# STM32_Schematic.net
KiCad netlist of a schematic drawn in Altium Designer
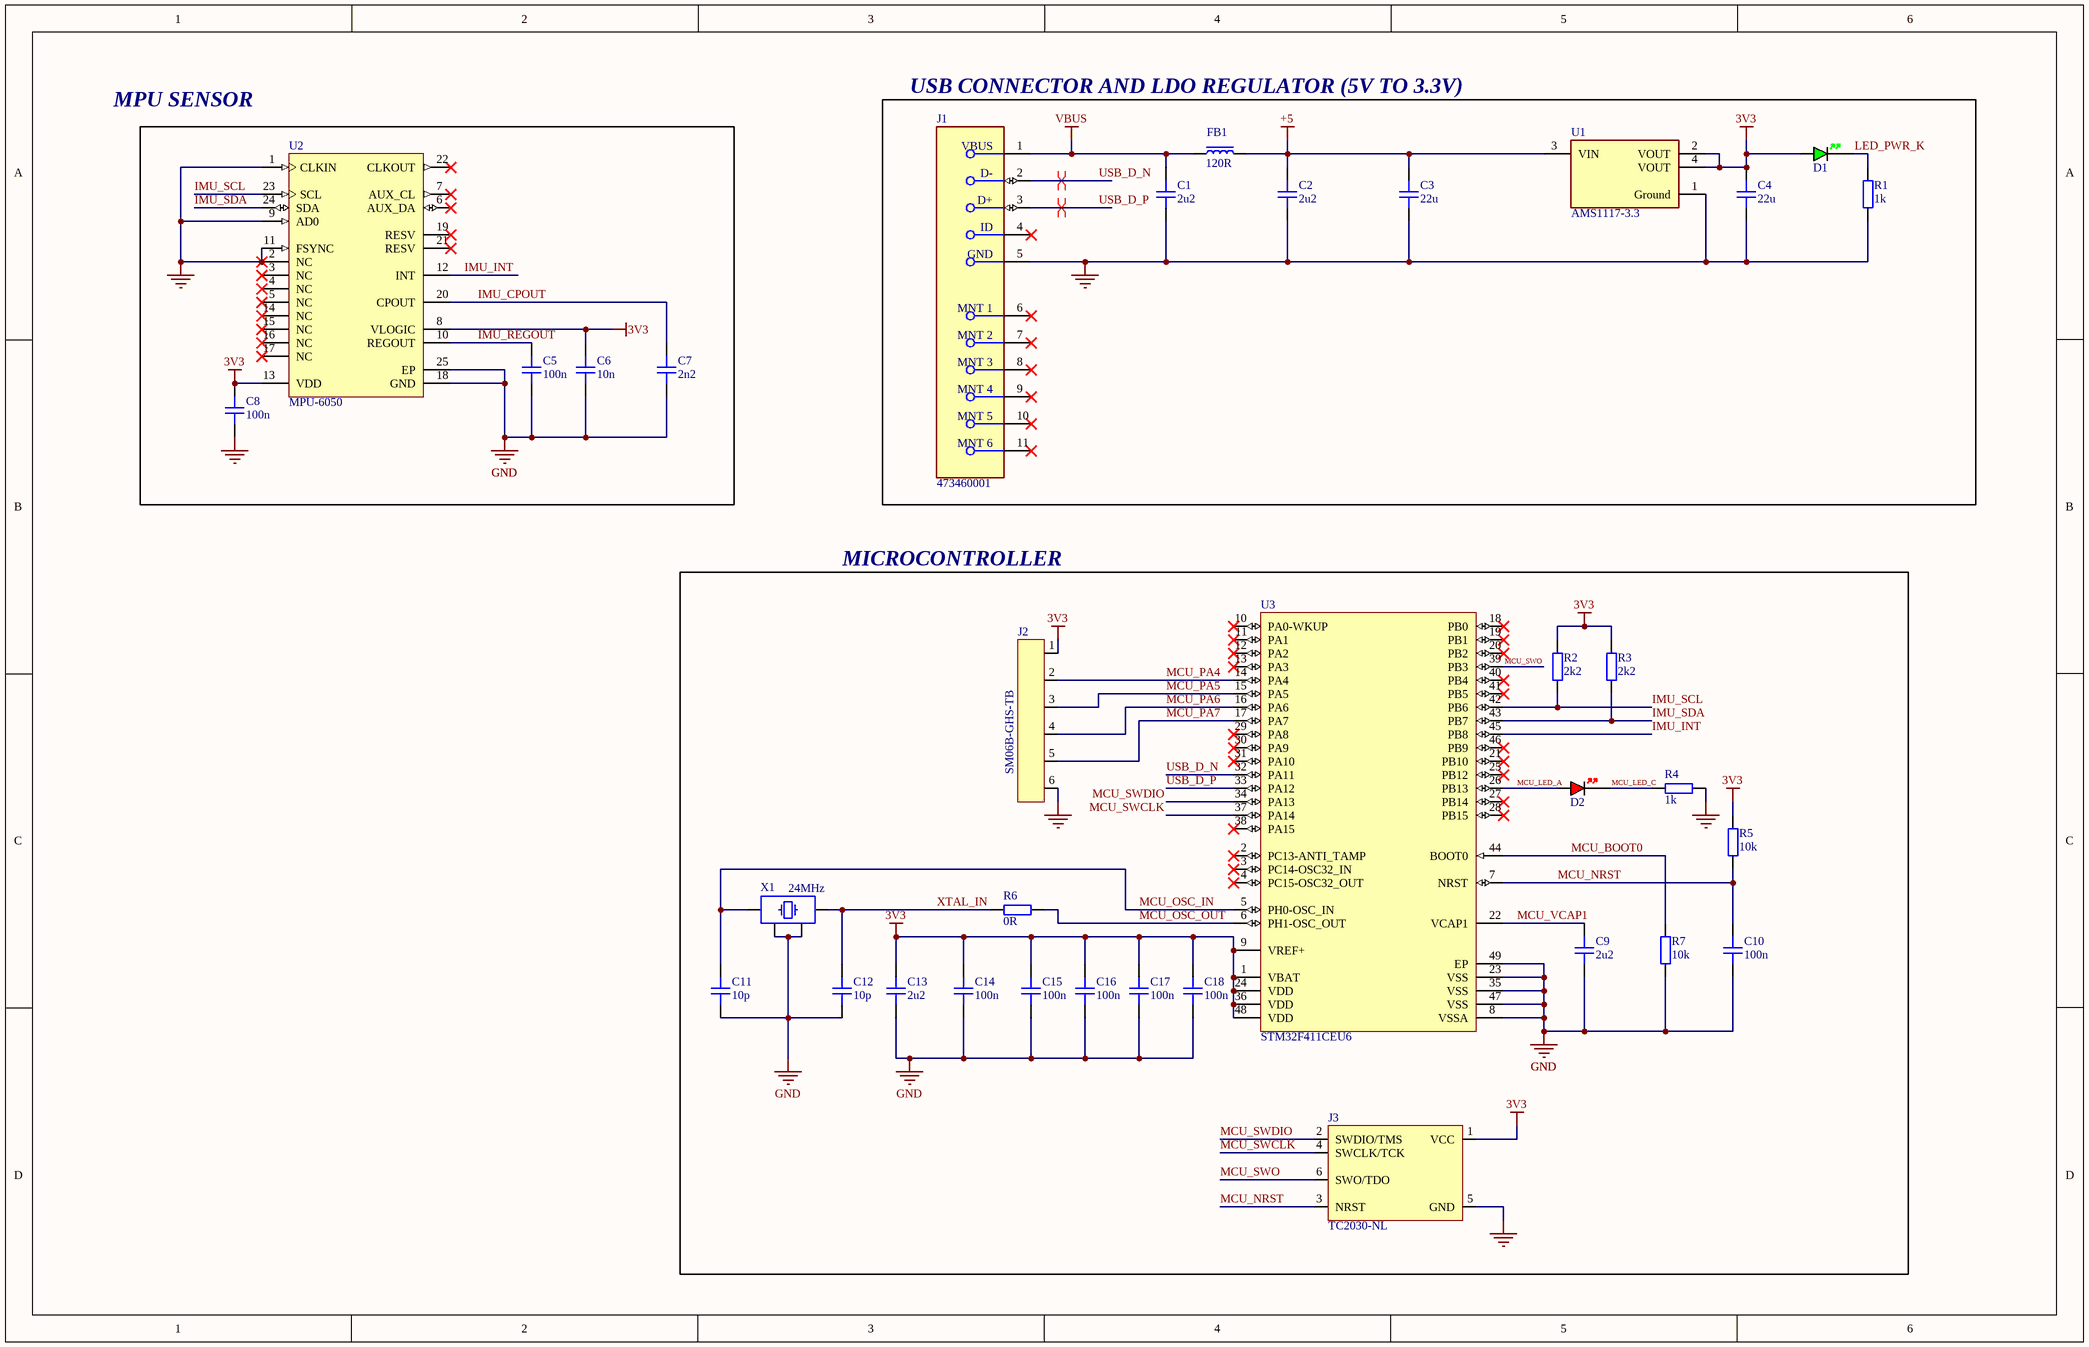
[diagram p0: STM32_Schematic.SchDoc]

(export (version "E")
  (design (tool "Eeschema 10.0.6"))
  (components
    (comp (ref "C1")
      (value "2u2")
      (footprint "CAP_0603")
      (description "Capacitor SMD 0603")
      (libsource (lib "Schematic-Lib-PhilsLab") (part "CAP_0603"))
    )
    (comp (ref "C2")
      (value "2u2")
      (footprint "CAP_0603")
      (description "Capacitor SMD 0603")
      (libsource (lib "Schematic-Lib-PhilsLab") (part "CAP_0603"))
    )
    (comp (ref "C3")
      (value "22u")
      (footprint "CAP_0805")
      (description "Capacitor SMD 0805")
      (libsource (lib "Schematic-Lib-PhilsLab") (part "CAP_0805"))
    )
    (comp (ref "C4")
      (value "22u")
      (footprint "CAP_0805")
      (description "Capacitor SMD 0805")
      (libsource (lib "Schematic-Lib-PhilsLab") (part "CAP_0805"))
    )
    (comp (ref "C5")
      (value "100n")
      (footprint "CAP_0402")
      (description "Capacitor SMD 0402")
      (libsource (lib "Schematic-Lib-PhilsLab") (part "CAP_0402"))
    )
    (comp (ref "C6")
      (value "10n")
      (footprint "CAP_0402")
      (description "Capacitor SMD 0402")
      (libsource (lib "Schematic-Lib-PhilsLab") (part "CAP_0402"))
    )
    (comp (ref "C7")
      (value "2n2")
      (footprint "CAP_0402")
      (description "Capacitor SMD 0402")
      (libsource (lib "Schematic-Lib-PhilsLab") (part "CAP_0402"))
    )
    (comp (ref "C8")
      (value "100n")
      (footprint "CAP_0402")
      (description "Capacitor SMD 0402")
      (libsource (lib "Schematic-Lib-PhilsLab") (part "CAP_0402"))
    )
    (comp (ref "C9")
      (value "2u2")
      (footprint "CAP_0603")
      (description "Capacitor SMD 0603")
      (libsource (lib "Schematic-Lib-PhilsLab") (part "CAP_0603"))
    )
    (comp (ref "C10")
      (value "100n")
      (footprint "CAP_0402")
      (description "Capacitor SMD 0402")
      (libsource (lib "Schematic-Lib-PhilsLab") (part "CAP_0402"))
    )
    (comp (ref "C11")
      (value "10p")
      (footprint "CAP_0402")
      (description "Capacitor SMD 0402")
      (libsource (lib "Schematic-Lib-PhilsLab") (part "CAP_0402"))
    )
    (comp (ref "C12")
      (value "10p")
      (footprint "CAP_0402")
      (description "Capacitor SMD 0402")
      (libsource (lib "Schematic-Lib-PhilsLab") (part "CAP_0402"))
    )
    (comp (ref "C13")
      (value "2u2")
      (footprint "CAP_0603")
      (description "Capacitor SMD 0603")
      (libsource (lib "Schematic-Lib-PhilsLab") (part "CAP_0603"))
    )
    (comp (ref "C14")
      (value "100n")
      (footprint "CAP_0402")
      (description "Capacitor SMD 0402")
      (libsource (lib "Schematic-Lib-PhilsLab") (part "CAP_0402"))
    )
    (comp (ref "C15")
      (value "100n")
      (footprint "CAP_0402")
      (description "Capacitor SMD 0402")
      (libsource (lib "Schematic-Lib-PhilsLab") (part "CAP_0402"))
    )
    (comp (ref "C16")
      (value "100n")
      (footprint "CAP_0402")
      (description "Capacitor SMD 0402")
      (libsource (lib "Schematic-Lib-PhilsLab") (part "CAP_0402"))
    )
    (comp (ref "C17")
      (value "100n")
      (footprint "CAP_0402")
      (description "Capacitor SMD 0402")
      (libsource (lib "Schematic-Lib-PhilsLab") (part "CAP_0402"))
    )
    (comp (ref "C18")
      (value "100n")
      (footprint "CAP_0402")
      (description "Capacitor SMD 0402")
      (libsource (lib "Schematic-Lib-PhilsLab") (part "CAP_0402"))
    )
    (comp (ref "D1")
      (value "GREEN")
      (footprint "LED_0402_GREEN")
      (description "LED 0402 GREEN SMD")
      (libsource (lib "Schematic-Lib-PhilsLab") (part "LED_0402_GREEN"))
    )
    (comp (ref "D2")
      (value "RED")
      (footprint "LED_0402_RED")
      (description "LED 0402 RED SMD")
      (libsource (lib "Schematic-Lib-PhilsLab") (part "LED_0402_RED"))
    )
    (comp (ref "FB1")
      (value "120R")
      (footprint "FB_0603")
      (description "Ferrite Bead SMD 0603")
      (libsource (lib "Schematic-Lib-PhilsLab") (part "FB_0603"))
    )
    (comp (ref "J1")
      (value "473460001")
      (footprint "FP-473460001-MFG")
      (description "CONN RCPT USB2.0 MICRO B SMD R/A")
      (fields
        (field (name "OCTOPART") "https://octopart.com/47346-0001-molex-7164928")
        (field (name "MANUFACTURER") "Molex")
      )
      (libsource (lib "Altium Content Vault") (part "53ae1f1d9b557310b43ca686e5bb76a"))
    )
    (comp (ref "J2")
      (value "SM06B-GHS-TB")
      (footprint "SM06B-GHS-TB")
      (description "Header Connector 6 Position 1.25MM Pitch SMD Horizontal JST GH")
      (fields (field (name "MANUFACTURER") "JST"))
      (libsource (lib "Schematic-Lib-PhilsLab") (part "SM06B-GHS-TB"))
    )
    (comp (ref "J3")
      (value "TC2030-NL")
      (footprint "TC2030-NL-FP")
      (description "Tag-Connect No-Solder SWD Debug Connector (No Legs) DO NOT PLACE")
      (fields
        (field (name "MANUFACTURER") "Tag-Connect")
        (field (name "MANUFACTURER PART NUMBER") "TC2030-NL-FP")
      )
      (libsource (lib "Schematic-Lib-PhilsLab") (part "TC2030-NL"))
    )
    (comp (ref "R1")
      (value "1k")
      (footprint "RES_0402")
      (description "Resistor SMD 0402")
      (libsource (lib "Schematic-Lib-PhilsLab") (part "RES_0402"))
    )
    (comp (ref "R2")
      (value "2k2")
      (footprint "RES_0402")
      (description "Resistor SMD 0402")
      (libsource (lib "Schematic-Lib-PhilsLab") (part "RES_0402"))
    )
    (comp (ref "R3")
      (value "2k2")
      (footprint "RES_0402")
      (description "Resistor SMD 0402")
      (libsource (lib "Schematic-Lib-PhilsLab") (part "RES_0402"))
    )
    (comp (ref "R4")
      (value "1k")
      (footprint "RES_0402")
      (description "Resistor SMD 0402")
      (libsource (lib "Schematic-Lib-PhilsLab") (part "RES_0402"))
    )
    (comp (ref "R5")
      (value "10k")
      (footprint "RES_0402")
      (description "Resistor SMD 0402")
      (libsource (lib "Schematic-Lib-PhilsLab") (part "RES_0402"))
    )
    (comp (ref "R6")
      (value "0R")
      (footprint "RES_0402")
      (description "Resistor SMD 0402")
      (libsource (lib "Schematic-Lib-PhilsLab") (part "RES_0402"))
    )
    (comp (ref "R7")
      (value "10k")
      (footprint "RES_0402")
      (description "Resistor SMD 0402")
      (libsource (lib "Schematic-Lib-PhilsLab") (part "RES_0402"))
    )
    (comp (ref "U1")
      (value "AMS1117-3.3")
      (footprint "FP-AMS1117-IPC_C")
      (description "LDO Voltage Regulators 1A, 3.3V")
      (fields
        (field (name "OCTOPART") "https://octopart.com/ams1117-3.3-advanced+monolithic+systems-25899300")
        (field (name "MANUFACTURER") "Advanced Monolithic Systems")
      )
      (libsource (lib "Altium Content Vault") (part "8bdbb5f8e77002000e30dd2845d0354"))
    )
    (comp (ref "U2")
      (value "MPU-6050")
      (footprint "IS-QFN-24_V")
      (fields (field (name "MANUFACTURER") "InvenSense"))
      (libsource (lib "Altium Content Vault") (part "IS-MPU-6050-QFN-24"))
    )
    (comp (ref "U3")
      (value "STM32F411CEU6")
      (footprint "STM-UFQFPN48_L")
      (libsource (lib "Altium Content Vault") (part "MC-ARM-STM32F411-UFQFPN48"))
    )
    (comp (ref "X1")
      (value "24MHz")
      (footprint "XTAL_3225")
      (description "Crystal SMD 24MHz 10PPM 7pF 3225")
      (fields
        (field (name "MANUFACTURER") "Epson")
        (field (name "MANUFACTURER PART NUMBER") "TSX-3225 24.0000MF15X-AC")
      )
      (libsource (lib "Schematic-Lib-PhilsLab") (part "TSX-3225_24.0000MF15X-AC"))
    )
  )
  (nets
    (net (code "1") (name "+5") (class "Default")
      (node (ref "C2") (pin "2") (pinfunction "2_2") (pintype "passive"))
      (node (ref "C3") (pin "1") (pinfunction "1_1") (pintype "passive"))
      (node (ref "FB1") (pin "2") (pinfunction "2_2") (pintype "passive"))
      (node (ref "U1") (pin "3") (pinfunction "VIN_3") (pintype "power_in"))
    )
    (net (code "2") (name "/IMU_CPOUT") (class "Default")
      (node (ref "C7") (pin "2") (pinfunction "2_2") (pintype "passive"))
      (node (ref "U2") (pin "20") (pinfunction "CPOUT_20") (pintype "passive"))
    )
    (net (code "3") (name "/IMU_INT") (class "Default")
      (node (ref "U2") (pin "12") (pinfunction "INT_12") (pintype "open_collector"))
      (node (ref "U3") (pin "45") (pinfunction "PB8_45") (pintype "bidirectional"))
    )
    (net (code "4") (name "/IMU_REGOUT") (class "Default")
      (node (ref "C5") (pin "2") (pinfunction "2_2") (pintype "passive"))
      (node (ref "U2") (pin "10") (pinfunction "REGOUT_10") (pintype "passive"))
    )
    (net (code "5") (name "/IMU_SCL") (class "Default")
      (node (ref "R2") (pin "1") (pinfunction "1_1") (pintype "passive"))
      (node (ref "U2") (pin "23") (pinfunction "SCL_23") (pintype "input"))
      (node (ref "U3") (pin "42") (pinfunction "PB6_42") (pintype "bidirectional"))
    )
    (net (code "6") (name "/IMU_SDA") (class "Default")
      (node (ref "R3") (pin "1") (pinfunction "1_1") (pintype "passive"))
      (node (ref "U2") (pin "24") (pinfunction "SDA_24") (pintype "bidirectional"))
      (node (ref "U3") (pin "43") (pinfunction "PB7_43") (pintype "bidirectional"))
    )
    (net (code "7") (name "/LED_PWR_K") (class "Default")
      (node (ref "D1") (pin "K") (pinfunction "K_K") (pintype "passive"))
      (node (ref "R1") (pin "2") (pinfunction "2_2") (pintype "passive"))
    )
    (net (code "8") (name "/MCU_BOOT0") (class "Default")
      (node (ref "R7") (pin "2") (pinfunction "2_2") (pintype "passive"))
      (node (ref "U3") (pin "44") (pinfunction "BOOT0_44") (pintype "input"))
    )
    (net (code "9") (name "/MCU_LED_A") (class "Default")
      (node (ref "D2") (pin "A") (pinfunction "A_A") (pintype "passive"))
      (node (ref "U3") (pin "26") (pinfunction "PB13_26") (pintype "bidirectional"))
    )
    (net (code "10") (name "/MCU_LED_C") (class "Default")
      (node (ref "D2") (pin "K") (pinfunction "K_K") (pintype "passive"))
      (node (ref "R4") (pin "2") (pinfunction "2_2") (pintype "passive"))
    )
    (net (code "11") (name "/MCU_NRST") (class "Default")
      (node (ref "C10") (pin "2") (pinfunction "2_2") (pintype "passive"))
      (node (ref "J3") (pin "3") (pinfunction "NRST_3") (pintype "passive"))
      (node (ref "R5") (pin "1") (pinfunction "1_1") (pintype "passive"))
      (node (ref "U3") (pin "7") (pinfunction "NRST_7") (pintype "bidirectional"))
    )
    (net (code "12") (name "/MCU_OSC_IN") (class "Default")
      (node (ref "C11") (pin "2") (pinfunction "2_2") (pintype "passive"))
      (node (ref "U3") (pin "5") (pinfunction "PH0-OSC_IN_5") (pintype "bidirectional"))
      (node (ref "X1") (pin "1") (pinfunction "1_1") (pintype "passive"))
    )
    (net (code "13") (name "/MCU_OSC_OUT") (class "Default")
      (node (ref "R6") (pin "2") (pinfunction "2_2") (pintype "passive"))
      (node (ref "U3") (pin "6") (pinfunction "PH1-OSC_OUT_6") (pintype "bidirectional"))
    )
    (net (code "14") (name "/MCU_PA4") (class "Default")
      (node (ref "J2") (pin "2") (pinfunction "2_2") (pintype "passive"))
      (node (ref "U3") (pin "14") (pinfunction "PA4_14") (pintype "bidirectional"))
    )
    (net (code "15") (name "/MCU_PA5") (class "Default")
      (node (ref "J2") (pin "3") (pinfunction "3_3") (pintype "passive"))
      (node (ref "U3") (pin "15") (pinfunction "PA5_15") (pintype "bidirectional"))
    )
    (net (code "16") (name "/MCU_PA6") (class "Default")
      (node (ref "J2") (pin "4") (pinfunction "4_4") (pintype "passive"))
      (node (ref "U3") (pin "16") (pinfunction "PA6_16") (pintype "bidirectional"))
    )
    (net (code "17") (name "/MCU_PA7") (class "Default")
      (node (ref "J2") (pin "5") (pinfunction "5_5") (pintype "passive"))
      (node (ref "U3") (pin "17") (pinfunction "PA7_17") (pintype "bidirectional"))
    )
    (net (code "18") (name "/MCU_SWCLK") (class "Default")
      (node (ref "J3") (pin "4") (pinfunction "SWCLK/TCK_4") (pintype "passive"))
      (node (ref "U3") (pin "37") (pinfunction "PA14_37") (pintype "bidirectional"))
    )
    (net (code "19") (name "/MCU_SWDIO") (class "Default")
      (node (ref "J3") (pin "2") (pinfunction "SWDIO/TMS_2") (pintype "passive"))
      (node (ref "U3") (pin "34") (pinfunction "PA13_34") (pintype "bidirectional"))
    )
    (net (code "20") (name "/MCU_SWO") (class "Default")
      (node (ref "J3") (pin "6") (pinfunction "SWO/TDO_6") (pintype "passive"))
      (node (ref "U3") (pin "39") (pinfunction "PB3_39") (pintype "bidirectional"))
    )
    (net (code "21") (name "/MCU_VCAP1") (class "Default")
      (node (ref "C9") (pin "2") (pinfunction "2_2") (pintype "passive"))
      (node (ref "U3") (pin "22") (pinfunction "VCAP1_22") (pintype "passive"))
    )
    (net (code "22") (name "/USB_D_N") (class "Default")
      (node (ref "J1") (pin "2") (pinfunction "D-_2") (pintype "bidirectional"))
      (node (ref "U3") (pin "32") (pinfunction "PA11_32") (pintype "bidirectional"))
    )
    (net (code "23") (name "/USB_D_P") (class "Default")
      (node (ref "J1") (pin "3") (pinfunction "D+_3") (pintype "bidirectional"))
      (node (ref "U3") (pin "33") (pinfunction "PA12_33") (pintype "bidirectional"))
    )
    (net (code "24") (name "/XTAL_IN") (class "Default")
      (node (ref "C12") (pin "2") (pinfunction "2_2") (pintype "passive"))
      (node (ref "R6") (pin "1") (pinfunction "1_1") (pintype "passive"))
      (node (ref "X1") (pin "3") (pinfunction "3_3") (pintype "passive"))
    )
    (net (code "25") (name "3V3") (class "Default")
      (node (ref "C13") (pin "2") (pinfunction "2_2") (pintype "passive"))
      (node (ref "C14") (pin "2") (pinfunction "2_2") (pintype "passive"))
      (node (ref "C15") (pin "2") (pinfunction "2_2") (pintype "passive"))
      (node (ref "C16") (pin "2") (pinfunction "2_2") (pintype "passive"))
      (node (ref "C17") (pin "2") (pinfunction "2_2") (pintype "passive"))
      (node (ref "C18") (pin "2") (pinfunction "2_2") (pintype "passive"))
      (node (ref "C4") (pin "1") (pinfunction "1_1") (pintype "passive"))
      (node (ref "C6") (pin "2") (pinfunction "2_2") (pintype "passive"))
      (node (ref "C8") (pin "2") (pinfunction "2_2") (pintype "passive"))
      (node (ref "D1") (pin "A") (pinfunction "A_A") (pintype "passive"))
      (node (ref "J2") (pin "1") (pinfunction "1_1") (pintype "passive"))
      (node (ref "J3") (pin "1") (pinfunction "VCC_1") (pintype "passive"))
      (node (ref "R2") (pin "2") (pinfunction "2_2") (pintype "passive"))
      (node (ref "R3") (pin "2") (pinfunction "2_2") (pintype "passive"))
      (node (ref "R5") (pin "2") (pinfunction "2_2") (pintype "passive"))
      (node (ref "U1") (pin "2") (pinfunction "VOUT_2") (pintype "passive"))
      (node (ref "U1") (pin "4") (pinfunction "VOUT_4") (pintype "passive"))
      (node (ref "U2") (pin "13") (pinfunction "VDD_13") (pintype "power_in"))
      (node (ref "U2") (pin "8") (pinfunction "VLOGIC_8") (pintype "power_in"))
      (node (ref "U3") (pin "1") (pinfunction "VBAT_1") (pintype "power_in"))
      (node (ref "U3") (pin "24") (pinfunction "VDD_24") (pintype "power_in"))
      (node (ref "U3") (pin "36") (pinfunction "VDD_36") (pintype "power_in"))
      (node (ref "U3") (pin "48") (pinfunction "VDD_48") (pintype "power_in"))
      (node (ref "U3") (pin "9") (pinfunction "VREF+_9") (pintype "power_in"))
    )
    (net (code "26") (name "GND") (class "Default")
      (node (ref "C1") (pin "1") (pinfunction "1_1") (pintype "passive"))
      (node (ref "C10") (pin "1") (pinfunction "1_1") (pintype "passive"))
      (node (ref "C11") (pin "1") (pinfunction "1_1") (pintype "passive"))
      (node (ref "C12") (pin "1") (pinfunction "1_1") (pintype "passive"))
      (node (ref "C13") (pin "1") (pinfunction "1_1") (pintype "passive"))
      (node (ref "C14") (pin "1") (pinfunction "1_1") (pintype "passive"))
      (node (ref "C15") (pin "1") (pinfunction "1_1") (pintype "passive"))
      (node (ref "C16") (pin "1") (pinfunction "1_1") (pintype "passive"))
      (node (ref "C17") (pin "1") (pinfunction "1_1") (pintype "passive"))
      (node (ref "C18") (pin "1") (pinfunction "1_1") (pintype "passive"))
      (node (ref "C2") (pin "1") (pinfunction "1_1") (pintype "passive"))
      (node (ref "C3") (pin "2") (pinfunction "2_2") (pintype "passive"))
      (node (ref "C4") (pin "2") (pinfunction "2_2") (pintype "passive"))
      (node (ref "C5") (pin "1") (pinfunction "1_1") (pintype "passive"))
      (node (ref "C6") (pin "1") (pinfunction "1_1") (pintype "passive"))
      (node (ref "C7") (pin "1") (pinfunction "1_1") (pintype "passive"))
      (node (ref "C8") (pin "1") (pinfunction "1_1") (pintype "passive"))
      (node (ref "C9") (pin "1") (pinfunction "1_1") (pintype "passive"))
      (node (ref "J1") (pin "5") (pinfunction "GND_5") (pintype "power_in"))
      (node (ref "J2") (pin "6") (pinfunction "6_6") (pintype "passive"))
      (node (ref "J3") (pin "5") (pinfunction "GND_5") (pintype "passive"))
      (node (ref "R1") (pin "1") (pinfunction "1_1") (pintype "passive"))
      (node (ref "R4") (pin "1") (pinfunction "1_1") (pintype "passive"))
      (node (ref "R7") (pin "1") (pinfunction "1_1") (pintype "passive"))
      (node (ref "U1") (pin "1") (pinfunction "Ground_1") (pintype "power_in"))
      (node (ref "U2") (pin "1") (pinfunction "CLKIN_1") (pintype "input"))
      (node (ref "U2") (pin "11") (pinfunction "FSYNC_11") (pintype "input"))
      (node (ref "U2") (pin "18") (pinfunction "GND_18") (pintype "power_in"))
      (node (ref "U2") (pin "2") (pinfunction "NC_2") (pintype "passive"))
      (node (ref "U2") (pin "25") (pinfunction "EP_25") (pintype "power_in"))
      (node (ref "U2") (pin "9") (pinfunction "AD0_9") (pintype "input"))
      (node (ref "U3") (pin "23") (pinfunction "VSS_23") (pintype "power_in"))
      (node (ref "U3") (pin "35") (pinfunction "VSS_35") (pintype "power_in"))
      (node (ref "U3") (pin "47") (pinfunction "VSS_47") (pintype "power_in"))
      (node (ref "U3") (pin "49") (pinfunction "EP_49") (pintype "power_in"))
      (node (ref "U3") (pin "8") (pinfunction "VSSA_8") (pintype "power_in"))
      (node (ref "X1") (pin "2") (pinfunction "2_2") (pintype "passive"))
      (node (ref "X1") (pin "4") (pinfunction "4_4") (pintype "passive"))
    )
    (net (code "27") (name "VBUS") (class "Default")
      (node (ref "C1") (pin "2") (pinfunction "2_2") (pintype "passive"))
      (node (ref "FB1") (pin "1") (pinfunction "1_1") (pintype "passive"))
      (node (ref "J1") (pin "1") (pinfunction "VBUS_1") (pintype "power_in"))
    )
    (net (code "28") (name "unconnected-(J1-ID-Pad4)") (class "Default")
      (node (ref "J1") (pin "4") (pinfunction "ID_4") (pintype "passive+no_connect"))
    )
    (net (code "29") (name "unconnected-(J1-MNT_1-Pad6)") (class "Default")
      (node (ref "J1") (pin "6") (pinfunction "MNT_1_6") (pintype "passive+no_connect"))
    )
    (net (code "30") (name "unconnected-(J1-MNT_2-Pad7)") (class "Default")
      (node (ref "J1") (pin "7") (pinfunction "MNT_2_7") (pintype "passive+no_connect"))
    )
    (net (code "31") (name "unconnected-(J1-MNT_3-Pad8)") (class "Default")
      (node (ref "J1") (pin "8") (pinfunction "MNT_3_8") (pintype "passive+no_connect"))
    )
    (net (code "32") (name "unconnected-(J1-MNT_4-Pad9)") (class "Default")
      (node (ref "J1") (pin "9") (pinfunction "MNT_4_9") (pintype "passive+no_connect"))
    )
    (net (code "33") (name "unconnected-(J1-MNT_5-Pad10)") (class "Default")
      (node (ref "J1") (pin "10") (pinfunction "MNT_5_10") (pintype "passive+no_connect"))
    )
    (net (code "34") (name "unconnected-(J1-MNT_6-Pad11)") (class "Default")
      (node (ref "J1") (pin "11") (pinfunction "MNT_6_11") (pintype "passive+no_connect"))
    )
    (net (code "35") (name "unconnected-(U2-AUX_CL-Pad7)") (class "Default")
      (node (ref "U2") (pin "7") (pinfunction "AUX_CL_7") (pintype "output+no_connect"))
    )
    (net (code "36") (name "unconnected-(U2-AUX_DA-Pad6)") (class "Default")
      (node (ref "U2") (pin "6") (pinfunction "AUX_DA_6") (pintype "bidirectional+no_connect"))
    )
    (net (code "37") (name "unconnected-(U2-CLKOUT-Pad22)") (class "Default")
      (node (ref "U2") (pin "22") (pinfunction "CLKOUT_22") (pintype "output+no_connect"))
    )
    (net (code "38") (name "unconnected-(U2-NC-Pad3)") (class "Default")
      (node (ref "U2") (pin "3") (pinfunction "NC_3") (pintype "passive+no_connect"))
    )
    (net (code "39") (name "unconnected-(U2-NC-Pad4)") (class "Default")
      (node (ref "U2") (pin "4") (pinfunction "NC_4") (pintype "passive+no_connect"))
    )
    (net (code "40") (name "unconnected-(U2-NC-Pad5)") (class "Default")
      (node (ref "U2") (pin "5") (pinfunction "NC_5") (pintype "passive+no_connect"))
    )
    (net (code "41") (name "unconnected-(U2-NC-Pad14)") (class "Default")
      (node (ref "U2") (pin "14") (pinfunction "NC_14") (pintype "passive+no_connect"))
    )
    (net (code "42") (name "unconnected-(U2-NC-Pad15)") (class "Default")
      (node (ref "U2") (pin "15") (pinfunction "NC_15") (pintype "passive+no_connect"))
    )
    (net (code "43") (name "unconnected-(U2-NC-Pad16)") (class "Default")
      (node (ref "U2") (pin "16") (pinfunction "NC_16") (pintype "passive+no_connect"))
    )
    (net (code "44") (name "unconnected-(U2-NC-Pad17)") (class "Default")
      (node (ref "U2") (pin "17") (pinfunction "NC_17") (pintype "passive+no_connect"))
    )
    (net (code "45") (name "unconnected-(U2-RESV-Pad19)") (class "Default")
      (node (ref "U2") (pin "19") (pinfunction "RESV_19") (pintype "passive+no_connect"))
    )
    (net (code "46") (name "unconnected-(U2-RESV-Pad21)") (class "Default")
      (node (ref "U2") (pin "21") (pinfunction "RESV_21") (pintype "passive+no_connect"))
    )
    (net (code "47") (name "unconnected-(U3-PA0-WKUP-Pad10)") (class "Default")
      (node (ref "U3") (pin "10") (pinfunction "PA0-WKUP_10") (pintype "bidirectional+no_connect"))
    )
    (net (code "48") (name "unconnected-(U3-PA1-Pad11)") (class "Default")
      (node (ref "U3") (pin "11") (pinfunction "PA1_11") (pintype "bidirectional+no_connect"))
    )
    (net (code "49") (name "unconnected-(U3-PA2-Pad12)") (class "Default")
      (node (ref "U3") (pin "12") (pinfunction "PA2_12") (pintype "bidirectional+no_connect"))
    )
    (net (code "50") (name "unconnected-(U3-PA3-Pad13)") (class "Default")
      (node (ref "U3") (pin "13") (pinfunction "PA3_13") (pintype "bidirectional+no_connect"))
    )
    (net (code "51") (name "unconnected-(U3-PA8-Pad29)") (class "Default")
      (node (ref "U3") (pin "29") (pinfunction "PA8_29") (pintype "bidirectional+no_connect"))
    )
    (net (code "52") (name "unconnected-(U3-PA9-Pad30)") (class "Default")
      (node (ref "U3") (pin "30") (pinfunction "PA9_30") (pintype "bidirectional+no_connect"))
    )
    (net (code "53") (name "unconnected-(U3-PA10-Pad31)") (class "Default")
      (node (ref "U3") (pin "31") (pinfunction "PA10_31") (pintype "bidirectional+no_connect"))
    )
    (net (code "54") (name "unconnected-(U3-PA15-Pad38)") (class "Default")
      (node (ref "U3") (pin "38") (pinfunction "PA15_38") (pintype "bidirectional+no_connect"))
    )
    (net (code "55") (name "unconnected-(U3-PB0-Pad18)") (class "Default")
      (node (ref "U3") (pin "18") (pinfunction "PB0_18") (pintype "bidirectional+no_connect"))
    )
    (net (code "56") (name "unconnected-(U3-PB1-Pad19)") (class "Default")
      (node (ref "U3") (pin "19") (pinfunction "PB1_19") (pintype "bidirectional+no_connect"))
    )
    (net (code "57") (name "unconnected-(U3-PB2-Pad20)") (class "Default")
      (node (ref "U3") (pin "20") (pinfunction "PB2_20") (pintype "bidirectional+no_connect"))
    )
    (net (code "58") (name "unconnected-(U3-PB4-Pad40)") (class "Default")
      (node (ref "U3") (pin "40") (pinfunction "PB4_40") (pintype "bidirectional+no_connect"))
    )
    (net (code "59") (name "unconnected-(U3-PB5-Pad41)") (class "Default")
      (node (ref "U3") (pin "41") (pinfunction "PB5_41") (pintype "bidirectional+no_connect"))
    )
    (net (code "60") (name "unconnected-(U3-PB9-Pad46)") (class "Default")
      (node (ref "U3") (pin "46") (pinfunction "PB9_46") (pintype "bidirectional+no_connect"))
    )
    (net (code "61") (name "unconnected-(U3-PB10-Pad21)") (class "Default")
      (node (ref "U3") (pin "21") (pinfunction "PB10_21") (pintype "bidirectional+no_connect"))
    )
    (net (code "62") (name "unconnected-(U3-PB12-Pad25)") (class "Default")
      (node (ref "U3") (pin "25") (pinfunction "PB12_25") (pintype "bidirectional+no_connect"))
    )
    (net (code "63") (name "unconnected-(U3-PB14-Pad27)") (class "Default")
      (node (ref "U3") (pin "27") (pinfunction "PB14_27") (pintype "bidirectional+no_connect"))
    )
    (net (code "64") (name "unconnected-(U3-PB15-Pad28)") (class "Default")
      (node (ref "U3") (pin "28") (pinfunction "PB15_28") (pintype "bidirectional+no_connect"))
    )
    (net (code "65") (name "unconnected-(U3-PC13-ANTI_TAMP-Pad2)") (class "Default")
      (node (ref "U3") (pin "2") (pinfunction "PC13-ANTI_TAMP_2") (pintype "bidirectional+no_connect"))
    )
    (net (code "66") (name "unconnected-(U3-PC14-OSC32_IN-Pad3)") (class "Default")
      (node (ref "U3") (pin "3") (pinfunction "PC14-OSC32_IN_3") (pintype "bidirectional+no_connect"))
    )
    (net (code "67") (name "unconnected-(U3-PC15-OSC32_OUT-Pad4)") (class "Default")
      (node (ref "U3") (pin "4") (pinfunction "PC15-OSC32_OUT_4") (pintype "bidirectional+no_connect"))
    )
  )
)
